# PSU_tracer.net
KiCad netlist of a schematic drawn in Altium Designer
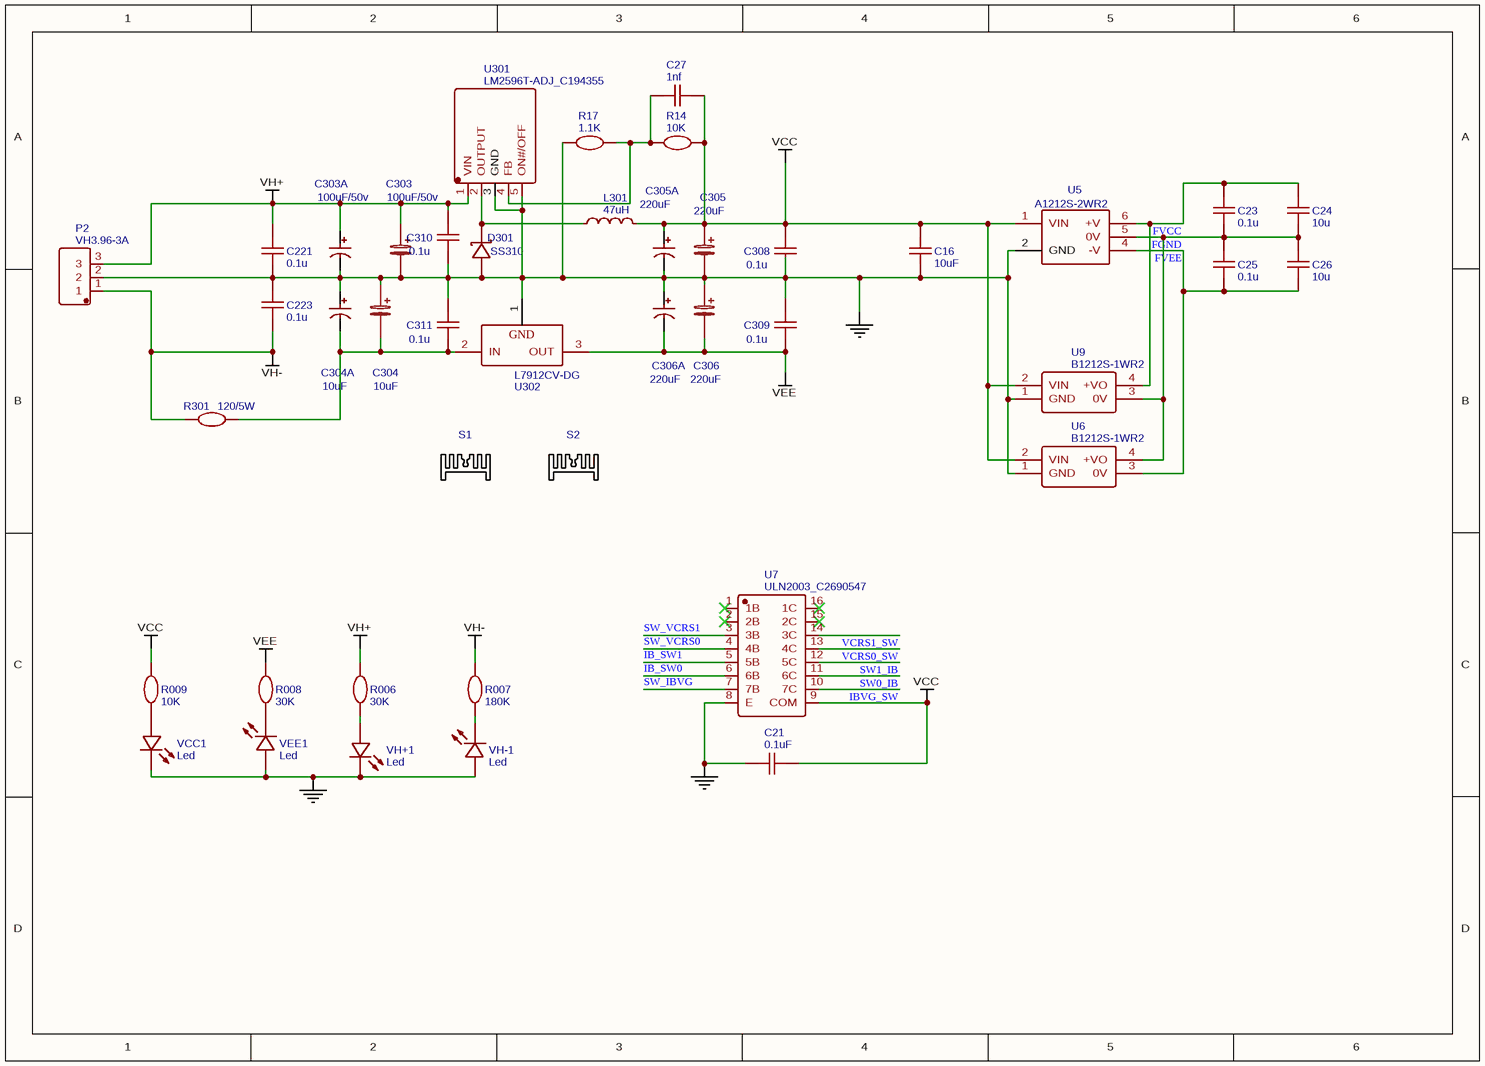
[diagram p0: PSU_tracer.schdoc]

(export (version "E")
  (design (tool "Eeschema 10.0.6"))
  (components
    (comp (ref "C16")
      (value "10uF")
      (footprint "C0805")
      (libsource (lib "altium-import") (part "root_0_10uF_"))
    )
    (comp (ref "C21")
      (value "0.1uF")
      (footprint "C0805")
      (libsource (lib "altium-import") (part "root_1_0.1uF_"))
    )
    (comp (ref "C23")
      (value "0.1u")
      (footprint "C0805")
      (libsource (lib "altium-import") (part "root_0_0.1u_"))
    )
    (comp (ref "C24")
      (value "10u")
      (footprint "C0805")
      (libsource (lib "altium-import") (part "root_0_10u_"))
    )
    (comp (ref "C25")
      (value "0.1u")
      (footprint "C0805")
      (libsource (lib "altium-import") (part "root_0_0.1u_"))
    )
    (comp (ref "C26")
      (value "10u")
      (footprint "C0805")
      (libsource (lib "altium-import") (part "root_0_10u_"))
    )
    (comp (ref "C27")
      (value "1nf")
      (footprint "C0805")
      (libsource (lib "altium-import") (part "root_1_1nf_"))
    )
    (comp (ref "C221")
      (value "0.1u")
      (footprint "RAD-0.2")
      (libsource (lib "altium-import") (part "root_0_0.1u_"))
    )
    (comp (ref "C223")
      (value "0.1u")
      (footprint "RAD-0.2")
      (libsource (lib "altium-import") (part "root_0_0.1u_"))
    )
    (comp (ref "C303")
      (value "100uF/50v")
      (footprint "CAP-TH_BD8.0-P3.50-D1.0-FD")
      (fields (field (name "CONTRIBUTOR") "LCEDA_Lib"))
      (libsource (lib "") (part "root_3_100uF/50v__1"))
    )
    (comp (ref "C303A")
      (value "100uF/50v")
      (footprint "CAP-TH_BD8.0-P2.50-D1.0-FD")
      (fields
        (field (name "BOM_MANUFACTURER PART") "100uF 16V 6.3*5")
        (field (name "BOM_SUPPLIER PART") "C43804")
      )
      (libsource (lib "altium-import") (part "root_3_100uF/50v_"))
    )
    (comp (ref "C304")
      (value "10uF")
      (footprint "CAP-TH_BD8.0-P3.50-D1.0-FD")
      (fields (field (name "CONTRIBUTOR") "LCEDA_Lib"))
      (libsource (lib "") (part "root_3_10uF__1"))
    )
    (comp (ref "C304A")
      (value "10uF")
      (footprint "CAP-TH_BD8.0-P2.50-D1.0-FD")
      (fields
        (field (name "BOM_MANUFACTURER PART") "100uF 16V 6.3*5")
        (field (name "BOM_SUPPLIER PART") "C43804")
      )
      (libsource (lib "altium-import") (part "root_3_10uF_"))
    )
    (comp (ref "C305")
      (value "220uF")
      (footprint "CAP-TH BD8.0-P3.50-D1.0-FD")
      (fields (field (name "CONTRIBUTOR") "LCEDA_Lib"))
      (libsource (lib "") (part "root_3_220uF__1"))
    )
    (comp (ref "C305A")
      (value "220uF")
      (footprint "CAP-TH_BD8.0-P2.50-D1.0-FD")
      (fields
        (field (name "BOM_MANUFACTURER PART") "100uF 16V 6.3*5")
        (field (name "BOM_SUPPLIER PART") "C43804")
      )
      (libsource (lib "altium-import") (part "root_3_220uF_"))
    )
    (comp (ref "C306")
      (value "220uF")
      (footprint "CAP-TH BD8.0-P3.50-D1.0-FD")
      (fields (field (name "CONTRIBUTOR") "LCEDA_Lib"))
      (libsource (lib "") (part "root_3_220uF__1"))
    )
    (comp (ref "C306A")
      (value "220uF")
      (footprint "CAP-TH_BD8.0-P2.50-D1.0-FD")
      (fields
        (field (name "BOM_MANUFACTURER PART") "100uF 16V 6.3*5")
        (field (name "BOM_SUPPLIER PART") "C43804")
      )
      (libsource (lib "altium-import") (part "root_3_220uF_"))
    )
    (comp (ref "C308")
      (value "0.1u")
      (footprint "C0805")
      (fields (field (name "CONTRIBUTOR") "LCEDA_Lib"))
      (libsource (lib "altium-import") (part "root_1_0.1u_"))
    )
    (comp (ref "C309")
      (value "0.1u")
      (footprint "C0805")
      (fields (field (name "CONTRIBUTOR") "LCEDA_Lib"))
      (libsource (lib "altium-import") (part "root_1_0.1u_"))
    )
    (comp (ref "C310")
      (value "0.1u")
      (footprint "C0805")
      (fields (field (name "CONTRIBUTOR") "LCEDA_Lib"))
      (libsource (lib "altium-import") (part "root_1_0.1u_"))
    )
    (comp (ref "C311")
      (value "0.1u")
      (footprint "C0805")
      (fields (field (name "CONTRIBUTOR") "LCEDA_Lib"))
      (libsource (lib "altium-import") (part "root_1_0.1u_"))
    )
    (comp (ref "D301")
      (value "SS310")
      (footprint "SMA_L4.3-W2.6-LS5.2-FD")
      (fields (field (name "BOM_MANUFACTURER PART") "SS110") (field (name "BOM_SUPPLIER PART") "C2482"))
      (libsource (lib "altium-import") (part "root_1_SS310_"))
    )
    (comp (ref "L301")
      (value "47uH")
      (footprint "IND-SMD_L11.5-W10.5_MWSA1004")
      (fields
        (field (name "BOM_SUPPLIER PART") "C380057")
        (field (name "BOM_MANUFACTURER PART") "MS1040-470M")
        (field (name "CONTRIBUTOR") "LCSC")
      )
      (libsource (lib "altium-import") (part "root_0_47uH_"))
    )
    (comp (ref "P2")
      (value "VH3.96-3A")
      (footprint "CONN-TH_3P-P3.96_VH3.96-3A")
      (fields (field (name "BOM_SUPPLIER PART") "C20547"))
      (libsource (lib "altium-import") (part "root_2_VH3.96-3A_"))
    )
    (comp (ref "R006")
      (value "30K")
      (footprint "R0805_NEW")
      (libsource (lib "altium-import") (part "root_3_30K_"))
    )
    (comp (ref "R007")
      (value "180K")
      (footprint "R0805_NEW")
      (libsource (lib "altium-import") (part "root_3_180K_"))
    )
    (comp (ref "R008")
      (value "30K")
      (footprint "R0805_NEW")
      (libsource (lib "altium-import") (part "root_3_30K_"))
    )
    (comp (ref "R009")
      (value "10K")
      (footprint "R0805_NEW")
      (libsource (lib "altium-import") (part "root_3_10K_"))
    )
    (comp (ref "R14")
      (value "10K")
      (footprint "R0805_NEW")
      (libsource (lib "altium-import") (part "root_0_10K_"))
    )
    (comp (ref "R17")
      (value "1.1K")
      (footprint "R0805_NEW")
      (libsource (lib "altium-import") (part "root_2_1.1K_"))
    )
    (comp (ref "R301")
      (value "120/5W")
      (footprint "R-AXIAL-1.2- 5W")
      (libsource (lib "altium-import") (part "root_0_120/5W_"))
    )
    (comp (ref "S1")
      (value "TO-220中点焊")
      (footprint "HEATSINK-TH_L23.5-W16.0-P18.0_XSD2156-067")
      (fields
        (field (name "BOM_MANUFACTURER PART") "TO-220散热片25*15*10")
        (field (name "贡献者") "Mxi")
        (field (name "CONTRIBUTOR") "PowerHGC")
      )
      (libsource (lib "altium-import") (part "root_0_TO-220中点焊_"))
    )
    (comp (ref "S2")
      (value "TO-220中点焊")
      (footprint "HEATSINK-TH_L23.5-W16.0-P18.0_XSD2156-067")
      (fields
        (field (name "BOM_MANUFACTURER PART") "TO-220散热片25*15*10")
        (field (name "贡献者") "Mxi")
        (field (name "CONTRIBUTOR") "PowerHGC")
      )
      (libsource (lib "altium-import") (part "root_0_TO-220中点焊_"))
    )
    (comp (ref "U5")
      (value "A1212S-2WR2")
      (footprint "PWRM-TH_A1212S-2WR2")
      (fields (field (name "BOM_SUPPLIER PART") "C41496"))
      (libsource (lib "altium-import") (part "root_0_A1212S-2WR2_"))
    )
    (comp (ref "U6")
      (value "B1212S-1WR2")
      (footprint "PWRM-TH_BXXXXS-1W")
      (fields (field (name "BOM_SUPPLIER PART") "C114073") (field (name "CONTRIBUTOR") "yuanshuo"))
      (libsource (lib "altium-import") (part "root_0_B1212S-1WR2_"))
    )
    (comp (ref "U7")
      (value "ULN2003_C2690547")
      (footprint "SOP-16_L10.0-W3.9-P1.27-LS6.0-BL")
      (fields
        (field (name "BOM_SUPPLIER PART") "C2690547")
        (field (name "BOM_MANUFACTURER PART") "ULN2003")
        (field (name "CONTRIBUTOR") "LCSC")
      )
      (libsource (lib "altium-import") (part "root_0_ULN2003_C2690547_"))
    )
    (comp (ref "U9")
      (value "B1212S-1WR2")
      (footprint "PWRM-TH_BXXXXS-1W")
      (fields (field (name "BOM_SUPPLIER PART") "C114073") (field (name "CONTRIBUTOR") "yuanshuo"))
      (libsource (lib "altium-import") (part "root_0_B1212S-1WR2_"))
    )
    (comp (ref "U301")
      (value "LM2596T-ADJ_C194355")
      (footprint "TO-220-5L_L10.2-W4.5-P1.71-L")
      (fields
        (field (name "BOM_SUPPLIER PART") "C194355")
        (field (name "BOM_MANUFACTURER PART") "LM2596T-ADJ")
        (field (name "CONTRIBUTOR") "LCSC")
      )
      (libsource (lib "altium-import") (part "root_1_LM2596T-ADJ_C194355_"))
    )
    (comp (ref "U302")
      (value "L7912CV-DG")
      (footprint "TO-220-3_L10.0-W4.5-P2.54-L")
      (fields (field (name "BOM_SUPPLIER PART") "C3797"))
      (libsource (lib "altium-import") (part "root_0_L7912CV-DG_"))
    )
    (comp (ref "VCC1")
      (value "Led")
      (footprint "LED-TH_BD4.0-P2.54-FD")
      (fields
        (field (name "BOM_SUPPLIER PART") "C396687")
        (field (name "BOM_MANUFACTURER PART") "DY-204URD/SN-A3(EL)")
        (field (name "CONTRIBUTOR") "LCSC")
      )
      (libsource (lib "altium-import") (part "root_3_Led_"))
    )
    (comp (ref "VEE1")
      (value "Led")
      (footprint "LED-TH_BD4.0-P2.54-FD")
      (fields
        (field (name "BOM_SUPPLIER PART") "C396687")
        (field (name "BOM_MANUFACTURER PART") "DY-204URD/SN-A3(EL)")
        (field (name "CONTRIBUTOR") "LCSC")
      )
      (libsource (lib "altium-import") (part "root_1_Led_"))
    )
    (comp (ref "VH+1")
      (value "Led")
      (footprint "LED-TH_BD4.0-P2.54-FD")
      (fields
        (field (name "BOM_SUPPLIER PART") "C396687")
        (field (name "BOM_MANUFACTURER PART") "DY-204URD/SN-A3(EL)")
        (field (name "CONTRIBUTOR") "LCSC")
      )
      (libsource (lib "altium-import") (part "root_3_Led_"))
    )
    (comp (ref "VH-1")
      (value "Led")
      (footprint "LED-TH_BD4.0-P2.54-FD")
      (fields
        (field (name "BOM_SUPPLIER PART") "C396687")
        (field (name "BOM_MANUFACTURER PART") "DY-204URD/SN-A3(EL)")
        (field (name "CONTRIBUTOR") "LCSC")
      )
      (libsource (lib "altium-import") (part "root_1_Led_"))
    )
  )
  (nets
    (net (code "1") (name "/FGND") (class "Default")
      (node (ref "C23") (pin "1") (pinfunction "1_1") (pintype "passive"))
      (node (ref "C24") (pin "1") (pinfunction "1_1") (pintype "passive"))
      (node (ref "C25") (pin "2") (pinfunction "2_2") (pintype "passive"))
      (node (ref "C26") (pin "2") (pinfunction "2_2") (pintype "passive"))
      (node (ref "U5") (pin "5") (pinfunction "0V_5") (pintype "passive"))
      (node (ref "U6") (pin "4") (pinfunction "+VO_4") (pintype "passive"))
      (node (ref "U9") (pin "3") (pinfunction "0V_3") (pintype "passive"))
    )
    (net (code "2") (name "/FVCC") (class "Default")
      (node (ref "C23") (pin "2") (pinfunction "2_2") (pintype "passive"))
      (node (ref "C24") (pin "2") (pinfunction "2_2") (pintype "passive"))
      (node (ref "U5") (pin "6") (pinfunction "+V_6") (pintype "passive"))
      (node (ref "U9") (pin "4") (pinfunction "+VO_4") (pintype "passive"))
    )
    (net (code "3") (name "/FVEE") (class "Default")
      (node (ref "C25") (pin "1") (pinfunction "1_1") (pintype "passive"))
      (node (ref "C26") (pin "1") (pinfunction "1_1") (pintype "passive"))
      (node (ref "U5") (pin "4") (pinfunction "-V_4") (pintype "passive"))
      (node (ref "U6") (pin "3") (pinfunction "0V_3") (pintype "passive"))
    )
    (net (code "4") (name "/IBVG_SW") (class "Default")
      (node (ref "U7") (pin "10") (pinfunction "7C_10") (pintype "passive"))
    )
    (net (code "5") (name "/IB_SW0") (class "Default")
      (node (ref "U7") (pin "6") (pinfunction "6B_6") (pintype "passive"))
    )
    (net (code "6") (name "/IB_SW1") (class "Default")
      (node (ref "U7") (pin "5") (pinfunction "5B_5") (pintype "passive"))
    )
    (net (code "7") (name "/SW0_IB") (class "Default")
      (node (ref "U7") (pin "11") (pinfunction "6C_11") (pintype "passive"))
    )
    (net (code "8") (name "/SW1_IB") (class "Default")
      (node (ref "U7") (pin "12") (pinfunction "5C_12") (pintype "passive"))
    )
    (net (code "9") (name "/SW_IBVG") (class "Default")
      (node (ref "U7") (pin "7") (pinfunction "7B_7") (pintype "passive"))
    )
    (net (code "10") (name "/SW_VCRS0") (class "Default")
      (node (ref "U7") (pin "4") (pinfunction "4B_4") (pintype "passive"))
    )
    (net (code "11") (name "/SW_VCRS1") (class "Default")
      (node (ref "U7") (pin "3") (pinfunction "3B_3") (pintype "passive"))
    )
    (net (code "12") (name "/VCRS0_SW") (class "Default")
      (node (ref "U7") (pin "13") (pinfunction "4C_13") (pintype "passive"))
    )
    (net (code "13") (name "/VCRS1_SW") (class "Default")
      (node (ref "U7") (pin "14") (pinfunction "3C_14") (pintype "passive"))
    )
    (net (code "14") (name "GND") (class "Default")
      (node (ref "C16") (pin "1") (pinfunction "1_1") (pintype "passive"))
      (node (ref "C21") (pin "2") (pinfunction "2_2") (pintype "passive"))
      (node (ref "C221") (pin "1") (pinfunction "1_1") (pintype "passive"))
      (node (ref "C223") (pin "2") (pinfunction "2_2") (pintype "passive"))
      (node (ref "C303") (pin "2") (pinfunction "2_2") (pintype "passive"))
      (node (ref "C303A") (pin "2") (pinfunction "2_2") (pintype "passive"))
      (node (ref "C304") (pin "1") (pinfunction "1_1") (pintype "passive"))
      (node (ref "C304A") (pin "1") (pinfunction "1_1") (pintype "passive"))
      (node (ref "C305") (pin "2") (pinfunction "2_2") (pintype "passive"))
      (node (ref "C305A") (pin "2") (pinfunction "2_2") (pintype "passive"))
      (node (ref "C306") (pin "1") (pinfunction "1_1") (pintype "passive"))
      (node (ref "C306A") (pin "1") (pinfunction "1_1") (pintype "passive"))
      (node (ref "C308") (pin "1") (pinfunction "1_1") (pintype "passive"))
      (node (ref "C309") (pin "2") (pinfunction "2_2") (pintype "passive"))
      (node (ref "C310") (pin "1") (pinfunction "1_1") (pintype "passive"))
      (node (ref "C311") (pin "2") (pinfunction "2_2") (pintype "passive"))
      (node (ref "D301") (pin "1") (pinfunction "A_1") (pintype "passive"))
      (node (ref "P2") (pin "2") (pinfunction "2_2") (pintype "passive"))
      (node (ref "R17") (pin "2") (pinfunction "2_2") (pintype "passive"))
      (node (ref "U301") (pin "3") (pinfunction "GND_3") (pintype "passive"))
      (node (ref "U301") (pin "5") (pinfunction "ON#/OFF_5") (pintype "passive"))
      (node (ref "U302") (pin "1") (pinfunction "GND_1") (pintype "passive"))
      (node (ref "U5") (pin "2") (pinfunction "GND_2") (pintype "passive"))
      (node (ref "U6") (pin "1") (pinfunction "GND_1") (pintype "passive"))
      (node (ref "U7") (pin "8") (pinfunction "E_8") (pintype "passive"))
      (node (ref "U9") (pin "1") (pinfunction "GND_1") (pintype "passive"))
      (node (ref "VCC1") (pin "2") (pinfunction "K_2") (pintype "passive"))
      (node (ref "VEE1") (pin "1") (pinfunction "A_1") (pintype "passive"))
      (node (ref "VH+1") (pin "2") (pinfunction "K_2") (pintype "passive"))
      (node (ref "VH-1") (pin "1") (pinfunction "A_1") (pintype "passive"))
    )
    (net (code "15") (name "Net-(D301-K)") (class "Default")
      (node (ref "D301") (pin "2") (pinfunction "K_2") (pintype "passive"))
      (node (ref "L301") (pin "1") (pinfunction "1_1") (pintype "passive"))
      (node (ref "U301") (pin "2") (pinfunction "OUTPUT_2") (pintype "passive"))
    )
    (net (code "16") (name "Net-(U301-FB)") (class "Default")
      (node (ref "C27") (pin "2") (pinfunction "2_2") (pintype "passive"))
      (node (ref "R14") (pin "1") (pinfunction "1_1") (pintype "passive"))
      (node (ref "R17") (pin "1") (pinfunction "1_1") (pintype "passive"))
      (node (ref "U301") (pin "4") (pinfunction "FB_4") (pintype "passive"))
    )
    (net (code "17") (name "Net-(U302-IN)") (class "Default")
      (node (ref "C304") (pin "2") (pinfunction "2_2") (pintype "passive"))
      (node (ref "C304A") (pin "2") (pinfunction "2_2") (pintype "passive"))
      (node (ref "C311") (pin "1") (pinfunction "1_1") (pintype "passive"))
      (node (ref "R301") (pin "2") (pinfunction "2_2") (pintype "passive"))
      (node (ref "U302") (pin "2") (pinfunction "IN_2") (pintype "passive"))
    )
    (net (code "18") (name "Net-(VCC1-A)") (class "Default")
      (node (ref "R009") (pin "2") (pinfunction "2_2") (pintype "passive"))
      (node (ref "VCC1") (pin "1") (pinfunction "A_1") (pintype "passive"))
    )
    (net (code "19") (name "Net-(VEE1-K)") (class "Default")
      (node (ref "R008") (pin "2") (pinfunction "2_2") (pintype "passive"))
      (node (ref "VEE1") (pin "2") (pinfunction "K_2") (pintype "passive"))
    )
    (net (code "20") (name "Net-(VH+1-A)") (class "Default")
      (node (ref "R006") (pin "2") (pinfunction "2_2") (pintype "passive"))
      (node (ref "VH+1") (pin "1") (pinfunction "A_1") (pintype "passive"))
    )
    (net (code "21") (name "Net-(VH-1-K)") (class "Default")
      (node (ref "R007") (pin "2") (pinfunction "2_2") (pintype "passive"))
      (node (ref "VH-1") (pin "2") (pinfunction "K_2") (pintype "passive"))
    )
    (net (code "22") (name "VCC") (class "Default")
      (node (ref "C16") (pin "2") (pinfunction "2_2") (pintype "passive"))
      (node (ref "C21") (pin "1") (pinfunction "1_1") (pintype "passive"))
      (node (ref "C27") (pin "1") (pinfunction "1_1") (pintype "passive"))
      (node (ref "C305") (pin "1") (pinfunction "1_1") (pintype "passive"))
      (node (ref "C305A") (pin "1") (pinfunction "1_1") (pintype "passive"))
      (node (ref "C308") (pin "2") (pinfunction "2_2") (pintype "passive"))
      (node (ref "L301") (pin "2") (pinfunction "2_2") (pintype "passive"))
      (node (ref "R009") (pin "1") (pinfunction "1_1") (pintype "passive"))
      (node (ref "R14") (pin "2") (pinfunction "2_2") (pintype "passive"))
      (node (ref "U5") (pin "1") (pinfunction "VIN_1") (pintype "passive"))
      (node (ref "U6") (pin "2") (pinfunction "VIN_2") (pintype "passive"))
      (node (ref "U7") (pin "9") (pinfunction "COM_9") (pintype "passive"))
      (node (ref "U9") (pin "2") (pinfunction "VIN_2") (pintype "passive"))
    )
    (net (code "23") (name "VEE") (class "Default")
      (node (ref "C306") (pin "2") (pinfunction "2_2") (pintype "passive"))
      (node (ref "C306A") (pin "2") (pinfunction "2_2") (pintype "passive"))
      (node (ref "C309") (pin "1") (pinfunction "1_1") (pintype "passive"))
      (node (ref "R008") (pin "1") (pinfunction "1_1") (pintype "passive"))
      (node (ref "U302") (pin "3") (pinfunction "OUT_3") (pintype "passive"))
    )
    (net (code "24") (name "VH+") (class "Default")
      (node (ref "C221") (pin "2") (pinfunction "2_2") (pintype "passive"))
      (node (ref "C303") (pin "1") (pinfunction "1_1") (pintype "passive"))
      (node (ref "C303A") (pin "1") (pinfunction "1_1") (pintype "passive"))
      (node (ref "C310") (pin "2") (pinfunction "2_2") (pintype "passive"))
      (node (ref "P2") (pin "3") (pinfunction "3_3") (pintype "passive"))
      (node (ref "R006") (pin "1") (pinfunction "1_1") (pintype "passive"))
      (node (ref "U301") (pin "1") (pinfunction "VIN_1") (pintype "passive"))
    )
    (net (code "25") (name "VH-") (class "Default")
      (node (ref "C223") (pin "1") (pinfunction "1_1") (pintype "passive"))
      (node (ref "P2") (pin "1") (pinfunction "1_1") (pintype "passive"))
      (node (ref "R007") (pin "1") (pinfunction "1_1") (pintype "passive"))
      (node (ref "R301") (pin "1") (pinfunction "1_1") (pintype "passive"))
    )
    (net (code "26") (name "unconnected-(U7-1B-Pad1)") (class "Default")
      (node (ref "U7") (pin "1") (pinfunction "1B_1") (pintype "passive+no_connect"))
    )
    (net (code "27") (name "unconnected-(U7-1C-Pad16)") (class "Default")
      (node (ref "U7") (pin "16") (pinfunction "1C_16") (pintype "passive+no_connect"))
    )
    (net (code "28") (name "unconnected-(U7-2B-Pad2)") (class "Default")
      (node (ref "U7") (pin "2") (pinfunction "2B_2") (pintype "passive+no_connect"))
    )
    (net (code "29") (name "unconnected-(U7-2C-Pad15)") (class "Default")
      (node (ref "U7") (pin "15") (pinfunction "2C_15") (pintype "passive+no_connect"))
    )
  )
)
